# 03_NOTECARD-CONNECTION.net
KiCad netlist of a schematic drawn in Altium Designer
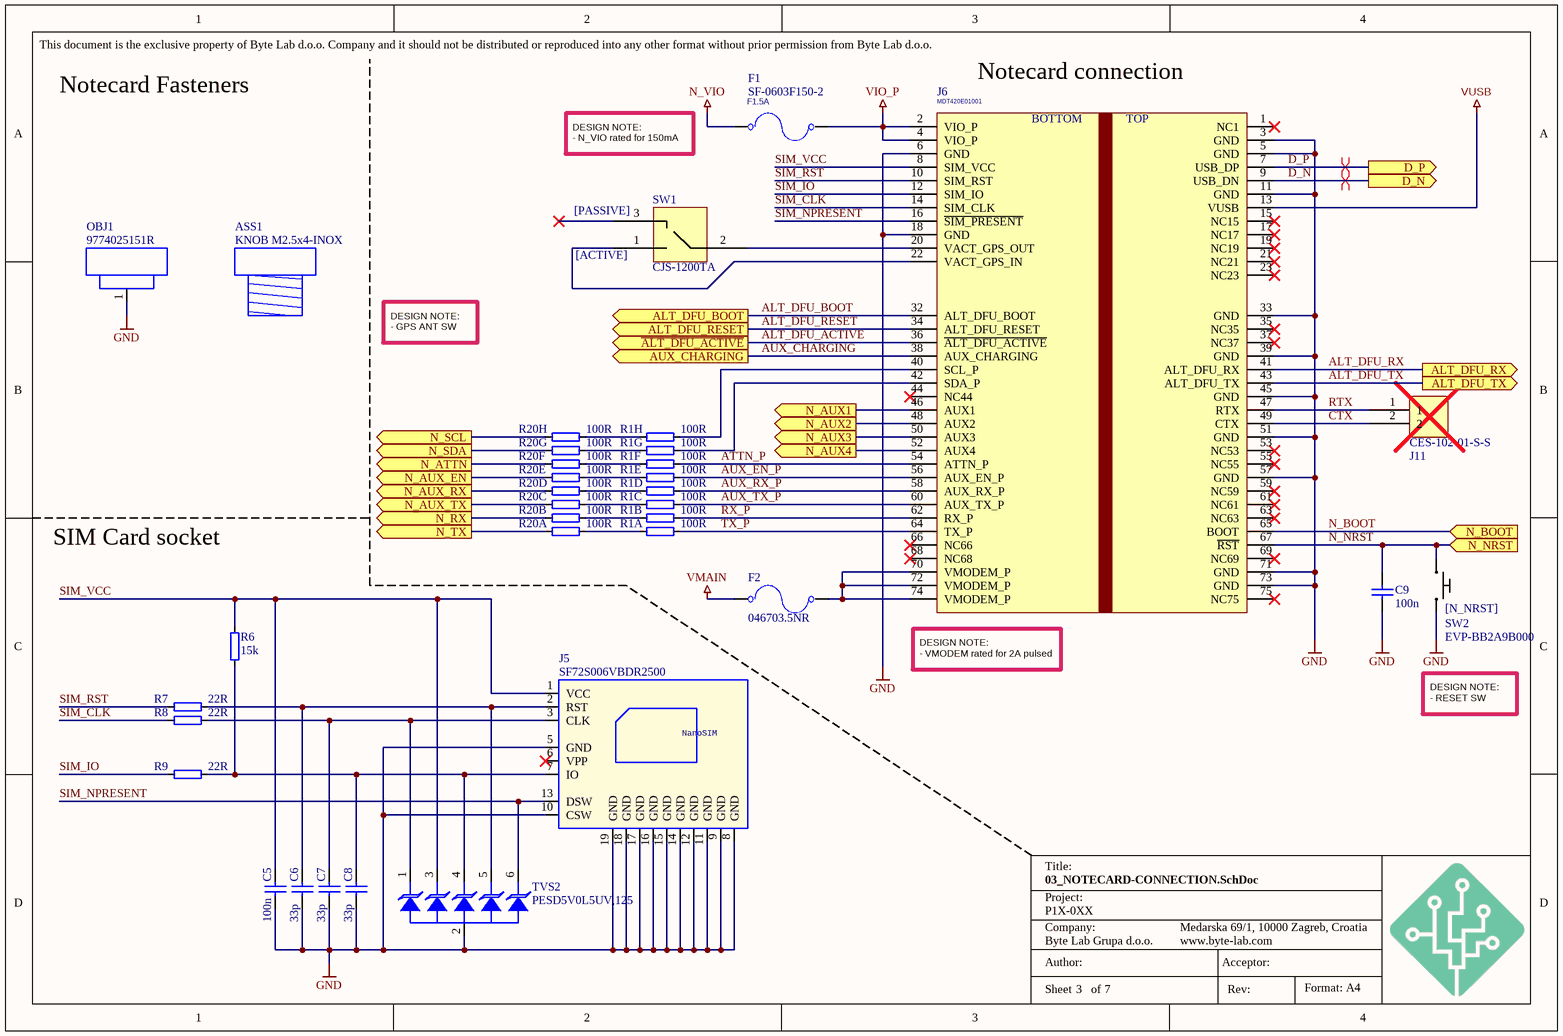
[diagram p0: 03_NOTECARD-CONNECTION.SchDoc]

(export (version "E")
  (design (tool "Eeschema 10.0.6"))
  (components
    (comp (ref "ASS1")
      (value "KNOB M2.5x4-INOX")
      (description "VITE TCEI 2.5X4 ESAGONO INCASSATO A2 INOX")
      (fields
        (field (name "MANUFACTURER PART NUMBER") "M2.5X4/D7985-A2")
        (field (name "MANUFACTURER") "KRAFTBERG")
        (field (name "DRAWN_BY") "Blues Wireless")
      )
      (libsource (lib "n21-p2") (part "KNOB - M2.5x4-INOX"))
    )
    (comp (ref "C5")
      (value "100n")
      (footprint "C-0402")
      (description "Capacitor ceramic 100n ±10% X7R 16V 0402")
      (fields
        (field (name "BL PART NUMBER") "2000-908")
        (field (name "DRAWN_BY") "Puskar")
        (field (name "CHECKED_BY") "Dodig")
      )
      (libsource (lib "BL_Passive") (part "C0402-100n-16V-X7R"))
    )
    (comp (ref "C6")
      (value "33p")
      (footprint "C-0402")
      (description "Capacitor ceramic 33p ±5% C0G 50V 0402")
      (fields
        (field (name "BL PART NUMBER") "2001-377")
        (field (name "DRAWN_BY") "Puskar")
        (field (name "CHECKED_BY") "Dodig")
      )
      (libsource (lib "BL_Passive") (part "C0402-33p-50V-C0G-5"))
    )
    (comp (ref "C7")
      (value "33p")
      (footprint "C-0402")
      (description "Capacitor ceramic 33p ±5% C0G 50V 0402")
      (fields
        (field (name "BL PART NUMBER") "2001-377")
        (field (name "DRAWN_BY") "Puskar")
        (field (name "CHECKED_BY") "Dodig")
      )
      (libsource (lib "BL_Passive") (part "C0402-33p-50V-C0G-5"))
    )
    (comp (ref "C8")
      (value "33p")
      (footprint "C-0402")
      (description "Capacitor ceramic 33p ±5% C0G 50V 0402")
      (fields
        (field (name "BL PART NUMBER") "2001-377")
        (field (name "DRAWN_BY") "Puskar")
        (field (name "CHECKED_BY") "Dodig")
      )
      (libsource (lib "BL_Passive") (part "C0402-33p-50V-C0G-5"))
    )
    (comp (ref "C9")
      (value "100n")
      (footprint "C-0402")
      (description "Capacitor ceramic 100n ±10% X7R 16V 0402")
      (fields
        (field (name "BL PART NUMBER") "2000-908")
        (field (name "DRAWN_BY") "Puskar")
        (field (name "CHECKED_BY") "Dodig")
      )
      (libsource (lib "BL_Passive") (part "C0402-100n-16V-X7R"))
    )
    (comp (ref "F1")
      (value "SF-0603F150-2")
      (footprint "FS-0603")
      (description "FUSIBILE RAPIDO 1.5A 32V 0603 SF-0603F150-2 BOURNS SMT")
      (fields
        (field (name "MANUFACTURER") "Bourns Inc.")
        (field (name "BL PART NUMBER") "2007-468")
        (field (name "DRAWN_BY") "Blues Wireless")
      )
      (libsource (lib "n21-p2") (part "RAPIDO - SF-0603F150-2-1.5A/32V"))
    )
    (comp (ref "F2")
      (value "046703.5NR")
      (footprint "FS-0603")
      (description "Fuse Chip Very Fast Acting 3.5A 32V SMD Solder Pad 0603 T/R CSA")
      (fields
        (field (name "MANUFACTURER") "Littelfuse Inc.")
        (field (name "BL PART NUMBER") "2007-469")
        (field (name "DRAWN_BY") "Blues Wireless")
      )
      (libsource (lib "n21-p2") (part "046703.5NR"))
    )
    (comp (ref "J5")
      (value "SF72S006VBDR2500")
      (footprint "J-NANOSIM-SF72S006VBA")
      (description "CONN. NANOSIM 8P F/90° PUSH-PUSH SF72S006VBAR2500 JAE ELECTRONICS SMT")
      (fields
        (field (name "MANUFACTURER") "JAE Electronics")
        (field (name "BL PART NUMBER") "2007-458")
        (field (name "DRAWN_BY") "Blues Wireless")
      )
      (libsource (lib "n21-p2") (part "NANOSIM - J-NANOSIM-SF72S006VBA"))
    )
    (comp (ref "J6")
      (value "MDT420E01001")
      (footprint "J-75-0050-MOS-M2")
      (description "CONN. M.2 75P M/90° P=0.5 MDT420E01001 AMPHENOL SMT")
      (fields
        (field (name "MANUFACTURER") "Amphenol ICC (FCI)")
        (field (name "MANUFACTURER PART NUMBER") "MDT420E03001")
        (field (name "DRAWN_BY") "Blues Wireless")
      )
      (libsource (lib "n21-p2") (part "AMPHENOL-75 - M-2 KEY E_13"))
    )
    (comp (ref "J11")
      (value "CES-102-01-S-S")
      (footprint "CONN_02")
      (description "0,1\" 2 PIN Header")
      (fields
        (field (name "MANUFACTURER") "Samtec Inc.")
        (field (name "BL PART NUMBER") "2007-461")
        (field (name "DRAWN_BY") "Blues Wireless")
      )
      (libsource (lib "n21-p2") (part "CONN_02"))
    )
    (comp (ref "OBJ1")
      (value "9774025151R")
      (footprint "DIST-WASMSIM0250")
      (description "DISTANZ. CIL. METALLO 5.1X2.5 9774025151R W.E SMT")
      (fields
        (field (name "MANUFACTURER") "Würth Elektronik")
        (field (name "BL PART NUMBER") "6020-113")
        (field (name "DRAWN_BY") "Blues Wieless")
      )
      (libsource (lib "n21-p2") (part "DISTANZIALE - M2.5x0250"))
    )
    (comp (ref "R1")
      (value "100R")
      (footprint "RESCAV80P640X160X70-16N")
      (description "Resistor array 100R 5% 2506")
      (fields
        (field (name "MANUFACTURER PART NUMBER") "742C163101JP")
        (field (name "MANUFACTURER") "CTS Resistor Products")
        (field (name "CHECKED_BY") "Klaic")
        (field (name "DRAWN_BY") "Duracic")
      )
      (libsource (lib "BL_Passive") (part "RESCAV80P640X160X70-16N - 8x100R"))
    )
    (comp (ref "R6")
      (value "15k")
      (footprint "BL_Passive:R-0402")
      (description "Resistor 15k ±1% 0402")
      (fields
        (field (name "BL PART NUMBER") "2001-157")
        (field (name "CHECKED_BY") "Zvonc")
        (field (name "DRAWN_BY") "Puskar")
      )
      (libsource (lib "BL_Passive") (part "R0402-15k-1"))
    )
    (comp (ref "R7")
      (value "22R")
      (footprint "BL_Passive:R-0402")
      (description "Resistor 22R ±1% 0402")
      (fields
        (field (name "BL PART NUMBER") "2001-170")
        (field (name "CHECKED_BY") "Hamin")
        (field (name "DRAWN_BY") "Zvonc")
      )
      (libsource (lib "BL_Passive") (part "R0402-22R-1"))
    )
    (comp (ref "R8")
      (value "22R")
      (footprint "BL_Passive:R-0402")
      (description "Resistor 22R ±1% 0402")
      (fields
        (field (name "BL PART NUMBER") "2001-170")
        (field (name "CHECKED_BY") "Hamin")
        (field (name "DRAWN_BY") "Zvonc")
      )
      (libsource (lib "BL_Passive") (part "R0402-22R-1"))
    )
    (comp (ref "R9")
      (value "22R")
      (footprint "BL_Passive:R-0402")
      (description "Resistor 22R ±1% 0402")
      (fields
        (field (name "BL PART NUMBER") "2001-170")
        (field (name "CHECKED_BY") "Hamin")
        (field (name "DRAWN_BY") "Zvonc")
      )
      (libsource (lib "BL_Passive") (part "R0402-22R-1"))
    )
    (comp (ref "R20")
      (value "100R")
      (footprint "RESCAV80P640X160X70-16N")
      (description "Resistor array 100R 5% 2506")
      (fields
        (field (name "MANUFACTURER PART NUMBER") "742C163101JP")
        (field (name "MANUFACTURER") "CTS Resistor Products")
        (field (name "CHECKED_BY") "Klaic")
        (field (name "DRAWN_BY") "Duracic")
      )
      (libsource (lib "BL_Passive") (part "RESCAV80P640X160X70-16N - 8x100R"))
    )
    (comp (ref "SW1")
      (value "CJS-1200TA")
      (footprint "SW_CJS-1200TA")
      (description "Switch Slide N.O./N.C. SPDT Raised Slide 0.1A 24VDC J-Hook SMD Embossed T/R")
      (fields
        (field (name "MANUFACTURER") "Nidec Copal")
        (field (name "BL PART NUMBER") "2007-456")
        (field (name "DRAWN_BY") "Blues Wireless")
      )
      (libsource (lib "n21-p2") (part "CJS-1200TA"))
    )
    (comp (ref "SW2")
      (value "EVP-BB2A9B000")
      (footprint "BL_Mechanical:SW_EVP-BB2A9B000")
      (description "SWITCH TACTILE SPST-NO 0.02A 15V")
      (fields
        (field (name "MANUFACTURER") "Panasonic Electronic Components")
        (field (name "BL PART NUMBER") "2007-124")
        (field (name "DRAWN_BY") "Marsic")
        (field (name "CHECKED_BY") "Duracic")
      )
      (libsource (lib "BL_Mechanical") (part "Switch tact EVP-BB2A9B000"))
    )
    (comp (ref "TVS2")
      (value "PESD5V0L5UV,125")
      (footprint "SOT666")
      (description "PESD Series 25 W 5 V Uni-Directional Fivefold ESD Protection Diode Array SOT-666")
      (fields
        (field (name "MANUFACTURER") "Nexperia")
        (field (name "BL PART NUMBER") "2007-452")
        (field (name "DRAWN_BY") "Blues Wireless")
      )
      (libsource (lib "n21-p2") (part "PESD5V0L5UV,125"))
    )
  )
  (nets
    (net (code "1") (name "/ALT_DFU_BOOT") (class "Default")
      (node (ref "J6") (pin "32") (pinfunction "ALT_DFU_BOOT_32") (pintype "passive"))
    )
    (net (code "2") (name "/ALT_DFU_RESET") (class "Default")
      (node (ref "J6") (pin "34") (pinfunction "ALT_DFU_RESET_34") (pintype "passive"))
    )
    (net (code "3") (name "/ALT_DFU_RX") (class "Default")
      (node (ref "J6") (pin "41") (pinfunction "ALT_DFU_RX_41") (pintype "passive"))
    )
    (net (code "4") (name "/ALT_DFU_TX") (class "Default")
      (node (ref "J6") (pin "43") (pinfunction "ALT_DFU_TX_43") (pintype "passive"))
    )
    (net (code "5") (name "/ATTN_P") (class "Default")
      (node (ref "J6") (pin "54") (pinfunction "ATTN_P_54") (pintype "passive"))
      (node (ref "R1") (pin "11") (pintype "passive"))
    )
    (net (code "6") (name "/AUX_CHARGING") (class "Default")
      (node (ref "J6") (pin "38") (pinfunction "AUX_CHARGING_38") (pintype "passive"))
    )
    (net (code "7") (name "/AUX_EN_P") (class "Default")
      (node (ref "J6") (pin "56") (pinfunction "AUX_EN_P_56") (pintype "passive"))
      (node (ref "R1") (pin "12") (pintype "passive"))
    )
    (net (code "8") (name "/AUX_RX_P") (class "Default")
      (node (ref "J6") (pin "58") (pinfunction "AUX_RX_P_58") (pintype "passive"))
      (node (ref "R1") (pin "13") (pintype "passive"))
    )
    (net (code "9") (name "/AUX_TX_P") (class "Default")
      (node (ref "J6") (pin "60") (pinfunction "AUX_TX_P_60") (pintype "passive"))
      (node (ref "R1") (pin "14") (pintype "passive"))
    )
    (net (code "10") (name "/CTX") (class "Default")
      (node (ref "J11") (pin "2") (pinfunction "2_2") (pintype "passive"))
      (node (ref "J6") (pin "49") (pinfunction "CTX_49") (pintype "passive"))
    )
    (net (code "11") (name "/D_N") (class "Default")
      (node (ref "J6") (pin "9") (pinfunction "USB_DN_9") (pintype "passive"))
    )
    (net (code "12") (name "/D_P") (class "Default")
      (node (ref "J6") (pin "7") (pinfunction "USB_DP_7") (pintype "passive"))
    )
    (net (code "13") (name "/N_ATTN") (class "Default") (node (ref "R20") (pin "6") (pintype "passive")))
    (net (code "14") (name "/N_AUX1") (class "Default")
      (node (ref "J6") (pin "46") (pinfunction "AUX1_46") (pintype "passive"))
    )
    (net (code "15") (name "/N_AUX2") (class "Default")
      (node (ref "J6") (pin "48") (pinfunction "AUX2_48") (pintype "passive"))
    )
    (net (code "16") (name "/N_AUX3") (class "Default")
      (node (ref "J6") (pin "50") (pinfunction "AUX3_50") (pintype "passive"))
    )
    (net (code "17") (name "/N_AUX4") (class "Default")
      (node (ref "J6") (pin "52") (pinfunction "AUX4_52") (pintype "passive"))
    )
    (net (code "18") (name "/N_AUX_EN") (class "Default") (node (ref "R20") (pin "5") (pintype "passive")))
    (net (code "19") (name "/N_AUX_RX") (class "Default") (node (ref "R20") (pin "4") (pintype "passive")))
    (net (code "20") (name "/N_AUX_TX") (class "Default") (node (ref "R20") (pin "3") (pintype "passive")))
    (net (code "21") (name "/N_BOOT") (class "Default")
      (node (ref "J6") (pin "65") (pinfunction "BOOT_65") (pintype "passive"))
    )
    (net (code "22") (name "/N_NRST") (class "Default")
      (node (ref "C9") (pin "2") (pinfunction "2_2") (pintype "passive"))
      (node (ref "J6") (pin "67") (pinfunction "~{RST}_67") (pintype "passive"))
      (node (ref "SW2") (pin "1") (pinfunction "A_1") (pintype "passive"))
    )
    (net (code "23") (name "/N_RX") (class "Default") (node (ref "R20") (pin "2") (pintype "passive")))
    (net (code "24") (name "/N_SCL") (class "Default") (node (ref "R20") (pin "8") (pintype "passive")))
    (net (code "25") (name "/N_SDA") (class "Default") (node (ref "R20") (pin "7") (pintype "passive")))
    (net (code "26") (name "/N_TX") (class "Default") (node (ref "R20") (pin "1") (pintype "passive")))
    (net (code "27") (name "/RTX") (class "Default")
      (node (ref "J11") (pin "1") (pinfunction "1_1") (pintype "passive"))
      (node (ref "J6") (pin "47") (pinfunction "RTX_47") (pintype "passive"))
    )
    (net (code "28") (name "/RX_P") (class "Default")
      (node (ref "J6") (pin "62") (pinfunction "RX_P_62") (pintype "passive"))
      (node (ref "R1") (pin "15") (pintype "passive"))
    )
    (net (code "29") (name "/SIM_CLK") (class "Default")
      (node (ref "J6") (pin "14") (pinfunction "SIM_CLK_14") (pintype "passive"))
      (node (ref "R8") (pin "1") (pintype "passive"))
    )
    (net (code "30") (name "/SIM_IO") (class "Default")
      (node (ref "J6") (pin "12") (pinfunction "SIM_IO_12") (pintype "passive"))
      (node (ref "R9") (pin "1") (pintype "passive"))
    )
    (net (code "31") (name "/SIM_NPRESENT") (class "Default")
      (node (ref "J5") (pin "13") (pinfunction "DSW_13") (pintype "passive"))
      (node (ref "J6") (pin "16") (pinfunction "~{SIM_PRESENT}_16") (pintype "passive"))
      (node (ref "TVS2") (pin "6") (pinfunction "C6_6") (pintype "passive"))
    )
    (net (code "32") (name "/SIM_RST") (class "Default")
      (node (ref "J6") (pin "10") (pinfunction "SIM_RST_10") (pintype "passive"))
      (node (ref "R7") (pin "1") (pintype "passive"))
    )
    (net (code "33") (name "/SIM_VCC") (class "Default")
      (node (ref "C5") (pin "2") (pinfunction "2_2") (pintype "passive"))
      (node (ref "J5") (pin "1") (pinfunction "VCC_1") (pintype "power_in"))
      (node (ref "J6") (pin "8") (pinfunction "SIM_VCC_8") (pintype "passive"))
      (node (ref "R6") (pin "2") (pintype "passive"))
      (node (ref "TVS2") (pin "3") (pinfunction "C3_3") (pintype "passive"))
    )
    (net (code "34") (name "/TX_P") (class "Default")
      (node (ref "J6") (pin "64") (pinfunction "TX_P_64") (pintype "passive"))
      (node (ref "R1") (pin "16") (pintype "passive"))
    )
    (net (code "35") (name "/~{ALT_DFU_ACTIVE}") (class "Default")
      (node (ref "J6") (pin "36") (pinfunction "~{ALT_DFU_ACTIVE}_36") (pintype "passive"))
    )
    (net (code "36") (name "GND") (class "Default")
      (node (ref "C5") (pin "1") (pinfunction "1_1") (pintype "passive"))
      (node (ref "C6") (pin "1") (pinfunction "1_1") (pintype "passive"))
      (node (ref "C7") (pin "1") (pinfunction "1_1") (pintype "passive"))
      (node (ref "C8") (pin "1") (pinfunction "1_1") (pintype "passive"))
      (node (ref "C9") (pin "1") (pinfunction "1_1") (pintype "passive"))
      (node (ref "J5") (pin "10") (pinfunction "CSW_10") (pintype "passive"))
      (node (ref "J5") (pin "11") (pinfunction "GND_11") (pintype "power_in"))
      (node (ref "J5") (pin "12") (pinfunction "GND_12") (pintype "power_in"))
      (node (ref "J5") (pin "14") (pinfunction "GND_14") (pintype "power_in"))
      (node (ref "J5") (pin "15") (pinfunction "GND_15") (pintype "power_in"))
      (node (ref "J5") (pin "16") (pinfunction "GND_16") (pintype "power_in"))
      (node (ref "J5") (pin "17") (pinfunction "GND_17") (pintype "power_in"))
      (node (ref "J5") (pin "18") (pinfunction "GND_18") (pintype "power_in"))
      (node (ref "J5") (pin "19") (pinfunction "GND_19") (pintype "power_in"))
      (node (ref "J5") (pin "5") (pinfunction "GND_5") (pintype "power_in"))
      (node (ref "J5") (pin "8") (pinfunction "GND_8") (pintype "power_in"))
      (node (ref "J5") (pin "9") (pinfunction "GND_9") (pintype "power_in"))
      (node (ref "J6") (pin "11") (pinfunction "GND_11") (pintype "passive"))
      (node (ref "J6") (pin "18") (pinfunction "GND_18") (pintype "passive"))
      (node (ref "J6") (pin "3") (pinfunction "GND_3") (pintype "passive"))
      (node (ref "J6") (pin "33") (pinfunction "GND_33") (pintype "passive"))
      (node (ref "J6") (pin "39") (pinfunction "GND_39") (pintype "passive"))
      (node (ref "J6") (pin "45") (pinfunction "GND_45") (pintype "passive"))
      (node (ref "J6") (pin "5") (pinfunction "GND_5") (pintype "passive"))
      (node (ref "J6") (pin "51") (pinfunction "GND_51") (pintype "passive"))
      (node (ref "J6") (pin "57") (pinfunction "GND_57") (pintype "passive"))
      (node (ref "J6") (pin "6") (pinfunction "GND_6") (pintype "passive"))
      (node (ref "J6") (pin "71") (pinfunction "GND_71") (pintype "passive"))
      (node (ref "J6") (pin "73") (pinfunction "GND_73") (pintype "passive"))
      (node (ref "OBJ1") (pin "1") (pinfunction "1_1") (pintype "power_in"))
      (node (ref "SW2") (pin "2") (pinfunction "B_2") (pintype "passive"))
      (node (ref "TVS2") (pin "2") (pinfunction "A2_2") (pintype "passive"))
    )
    (net (code "37") (name "N_VIO") (class "Default")
      (node (ref "F1") (pin "1") (pinfunction "1_1") (pintype "passive"))
    )
    (net (code "38") (name "Net-(F2-Pad2)") (class "Default")
      (node (ref "F2") (pin "2") (pinfunction "2_2") (pintype "passive"))
      (node (ref "J6") (pin "70") (pinfunction "VMODEM_P_70") (pintype "passive"))
      (node (ref "J6") (pin "72") (pinfunction "VMODEM_P_72") (pintype "passive"))
      (node (ref "J6") (pin "74") (pinfunction "VMODEM_P_74") (pintype "passive"))
    )
    (net (code "39") (name "Net-(J5-CLK)") (class "Default")
      (node (ref "C7") (pin "2") (pinfunction "2_2") (pintype "passive"))
      (node (ref "J5") (pin "3") (pinfunction "CLK_3") (pintype "passive"))
      (node (ref "R8") (pin "2") (pintype "passive"))
      (node (ref "TVS2") (pin "1") (pinfunction "C1_1") (pintype "passive"))
    )
    (net (code "40") (name "Net-(J5-IO)") (class "Default")
      (node (ref "C8") (pin "2") (pinfunction "2_2") (pintype "passive"))
      (node (ref "J5") (pin "7") (pinfunction "IO_7") (pintype "bidirectional"))
      (node (ref "R6") (pin "1") (pintype "passive"))
      (node (ref "R9") (pin "2") (pintype "passive"))
      (node (ref "TVS2") (pin "4") (pinfunction "C4_4") (pintype "passive"))
    )
    (net (code "41") (name "Net-(J5-RST)") (class "Default")
      (node (ref "C6") (pin "2") (pinfunction "2_2") (pintype "passive"))
      (node (ref "J5") (pin "2") (pinfunction "RST_2") (pintype "passive"))
      (node (ref "R7") (pin "2") (pintype "passive"))
      (node (ref "TVS2") (pin "5") (pinfunction "A5_5") (pintype "passive"))
    )
    (net (code "42") (name "Net-(J6-SCL_P)") (class "Default")
      (node (ref "J6") (pin "40") (pinfunction "SCL_P_40") (pintype "passive"))
      (node (ref "R1") (pin "9") (pintype "passive"))
    )
    (net (code "43") (name "Net-(J6-SDA_P)") (class "Default")
      (node (ref "J6") (pin "42") (pinfunction "SDA_P_42") (pintype "passive"))
      (node (ref "R1") (pin "10") (pintype "passive"))
    )
    (net (code "44") (name "Net-(J6-VACT_GPS_IN)") (class "Default")
      (node (ref "J6") (pin "22") (pinfunction "VACT_GPS_IN_22") (pintype "passive"))
      (node (ref "SW1") (pin "1") (pinfunction "1_1") (pintype "passive"))
    )
    (net (code "45") (name "Net-(J6-VACT_GPS_OUT)") (class "Default")
      (node (ref "J6") (pin "20") (pinfunction "VACT_GPS_OUT_20") (pintype "passive"))
      (node (ref "SW1") (pin "2") (pinfunction "2_2") (pintype "passive"))
    )
    (net (code "46") (name "Net-(R1-Pad1)") (class "Default")
      (node (ref "R1") (pin "1") (pintype "passive"))
      (node (ref "R20") (pin "16") (pintype "passive"))
    )
    (net (code "47") (name "Net-(R1-Pad2)") (class "Default")
      (node (ref "R1") (pin "2") (pintype "passive"))
      (node (ref "R20") (pin "15") (pintype "passive"))
    )
    (net (code "48") (name "Net-(R1-Pad3)") (class "Default")
      (node (ref "R1") (pin "3") (pintype "passive"))
      (node (ref "R20") (pin "14") (pintype "passive"))
    )
    (net (code "49") (name "Net-(R1-Pad4)") (class "Default")
      (node (ref "R1") (pin "4") (pintype "passive"))
      (node (ref "R20") (pin "13") (pintype "passive"))
    )
    (net (code "50") (name "Net-(R1-Pad5)") (class "Default")
      (node (ref "R1") (pin "5") (pintype "passive"))
      (node (ref "R20") (pin "12") (pintype "passive"))
    )
    (net (code "51") (name "Net-(R1-Pad6)") (class "Default")
      (node (ref "R1") (pin "6") (pintype "passive"))
      (node (ref "R20") (pin "11") (pintype "passive"))
    )
    (net (code "52") (name "Net-(R1-Pad7)") (class "Default")
      (node (ref "R1") (pin "7") (pintype "passive"))
      (node (ref "R20") (pin "10") (pintype "passive"))
    )
    (net (code "53") (name "Net-(R1-Pad8)") (class "Default")
      (node (ref "R1") (pin "8") (pintype "passive"))
      (node (ref "R20") (pin "9") (pintype "passive"))
    )
    (net (code "54") (name "VIO_P") (class "Default")
      (node (ref "F1") (pin "2") (pinfunction "2_2") (pintype "passive"))
      (node (ref "J6") (pin "2") (pinfunction "VIO_P_2") (pintype "passive"))
      (node (ref "J6") (pin "4") (pinfunction "VIO_P_4") (pintype "passive"))
    )
    (net (code "55") (name "VMAIN") (class "Default")
      (node (ref "F2") (pin "1") (pinfunction "1_1") (pintype "passive"))
    )
    (net (code "56") (name "VUSB") (class "Default")
      (node (ref "J6") (pin "13") (pinfunction "VUSB_13") (pintype "passive"))
    )
    (net (code "57") (name "unconnected-(J5-VPP-Pad6)") (class "Default")
      (node (ref "J5") (pin "6") (pinfunction "VPP_6") (pintype "passive+no_connect"))
    )
    (net (code "58") (name "unconnected-(J6-NC1-Pad1)") (class "Default")
      (node (ref "J6") (pin "1") (pinfunction "NC1_1") (pintype "passive+no_connect"))
    )
    (net (code "59") (name "unconnected-(J6-NC15-Pad15)") (class "Default")
      (node (ref "J6") (pin "15") (pinfunction "NC15_15") (pintype "passive+no_connect"))
    )
    (net (code "60") (name "unconnected-(J6-NC17-Pad17)") (class "Default")
      (node (ref "J6") (pin "17") (pinfunction "NC17_17") (pintype "passive+no_connect"))
    )
    (net (code "61") (name "unconnected-(J6-NC19-Pad19)") (class "Default")
      (node (ref "J6") (pin "19") (pinfunction "NC19_19") (pintype "passive+no_connect"))
    )
    (net (code "62") (name "unconnected-(J6-NC21-Pad21)") (class "Default")
      (node (ref "J6") (pin "21") (pinfunction "NC21_21") (pintype "passive+no_connect"))
    )
    (net (code "63") (name "unconnected-(J6-NC23-Pad23)") (class "Default")
      (node (ref "J6") (pin "23") (pinfunction "NC23_23") (pintype "passive+no_connect"))
    )
    (net (code "64") (name "unconnected-(J6-NC35-Pad35)") (class "Default")
      (node (ref "J6") (pin "35") (pinfunction "NC35_35") (pintype "passive+no_connect"))
    )
    (net (code "65") (name "unconnected-(J6-NC37-Pad37)") (class "Default")
      (node (ref "J6") (pin "37") (pinfunction "NC37_37") (pintype "passive+no_connect"))
    )
    (net (code "66") (name "unconnected-(J6-NC44-Pad44)") (class "Default")
      (node (ref "J6") (pin "44") (pinfunction "NC44_44") (pintype "passive+no_connect"))
    )
    (net (code "67") (name "unconnected-(J6-NC53-Pad53)") (class "Default")
      (node (ref "J6") (pin "53") (pinfunction "NC53_53") (pintype "passive+no_connect"))
    )
    (net (code "68") (name "unconnected-(J6-NC55-Pad55)") (class "Default")
      (node (ref "J6") (pin "55") (pinfunction "NC55_55") (pintype "passive+no_connect"))
    )
    (net (code "69") (name "unconnected-(J6-NC59-Pad59)") (class "Default")
      (node (ref "J6") (pin "59") (pinfunction "NC59_59") (pintype "passive+no_connect"))
    )
    (net (code "70") (name "unconnected-(J6-NC61-Pad61)") (class "Default")
      (node (ref "J6") (pin "61") (pinfunction "NC61_61") (pintype "passive+no_connect"))
    )
    (net (code "71") (name "unconnected-(J6-NC63-Pad63)") (class "Default")
      (node (ref "J6") (pin "63") (pinfunction "NC63_63") (pintype "passive+no_connect"))
    )
    (net (code "72") (name "unconnected-(J6-NC66-Pad66)") (class "Default")
      (node (ref "J6") (pin "66") (pinfunction "NC66_66") (pintype "passive+no_connect"))
    )
    (net (code "73") (name "unconnected-(J6-NC68-Pad68)") (class "Default")
      (node (ref "J6") (pin "68") (pinfunction "NC68_68") (pintype "passive+no_connect"))
    )
    (net (code "74") (name "unconnected-(J6-NC69-Pad69)") (class "Default")
      (node (ref "J6") (pin "69") (pinfunction "NC69_69") (pintype "passive+no_connect"))
    )
    (net (code "75") (name "unconnected-(J6-NC75-Pad75)") (class "Default")
      (node (ref "J6") (pin "75") (pinfunction "NC75_75") (pintype "passive+no_connect"))
    )
    (net (code "76") (name "unconnected-(SW1-Pad3)") (class "Default")
      (node (ref "SW1") (pin "3") (pinfunction "3_3") (pintype "passive+no_connect"))
    )
  )
)
